# 07_-_CONNECTORS_2.net
KiCad netlist of a schematic drawn in Altium Designer
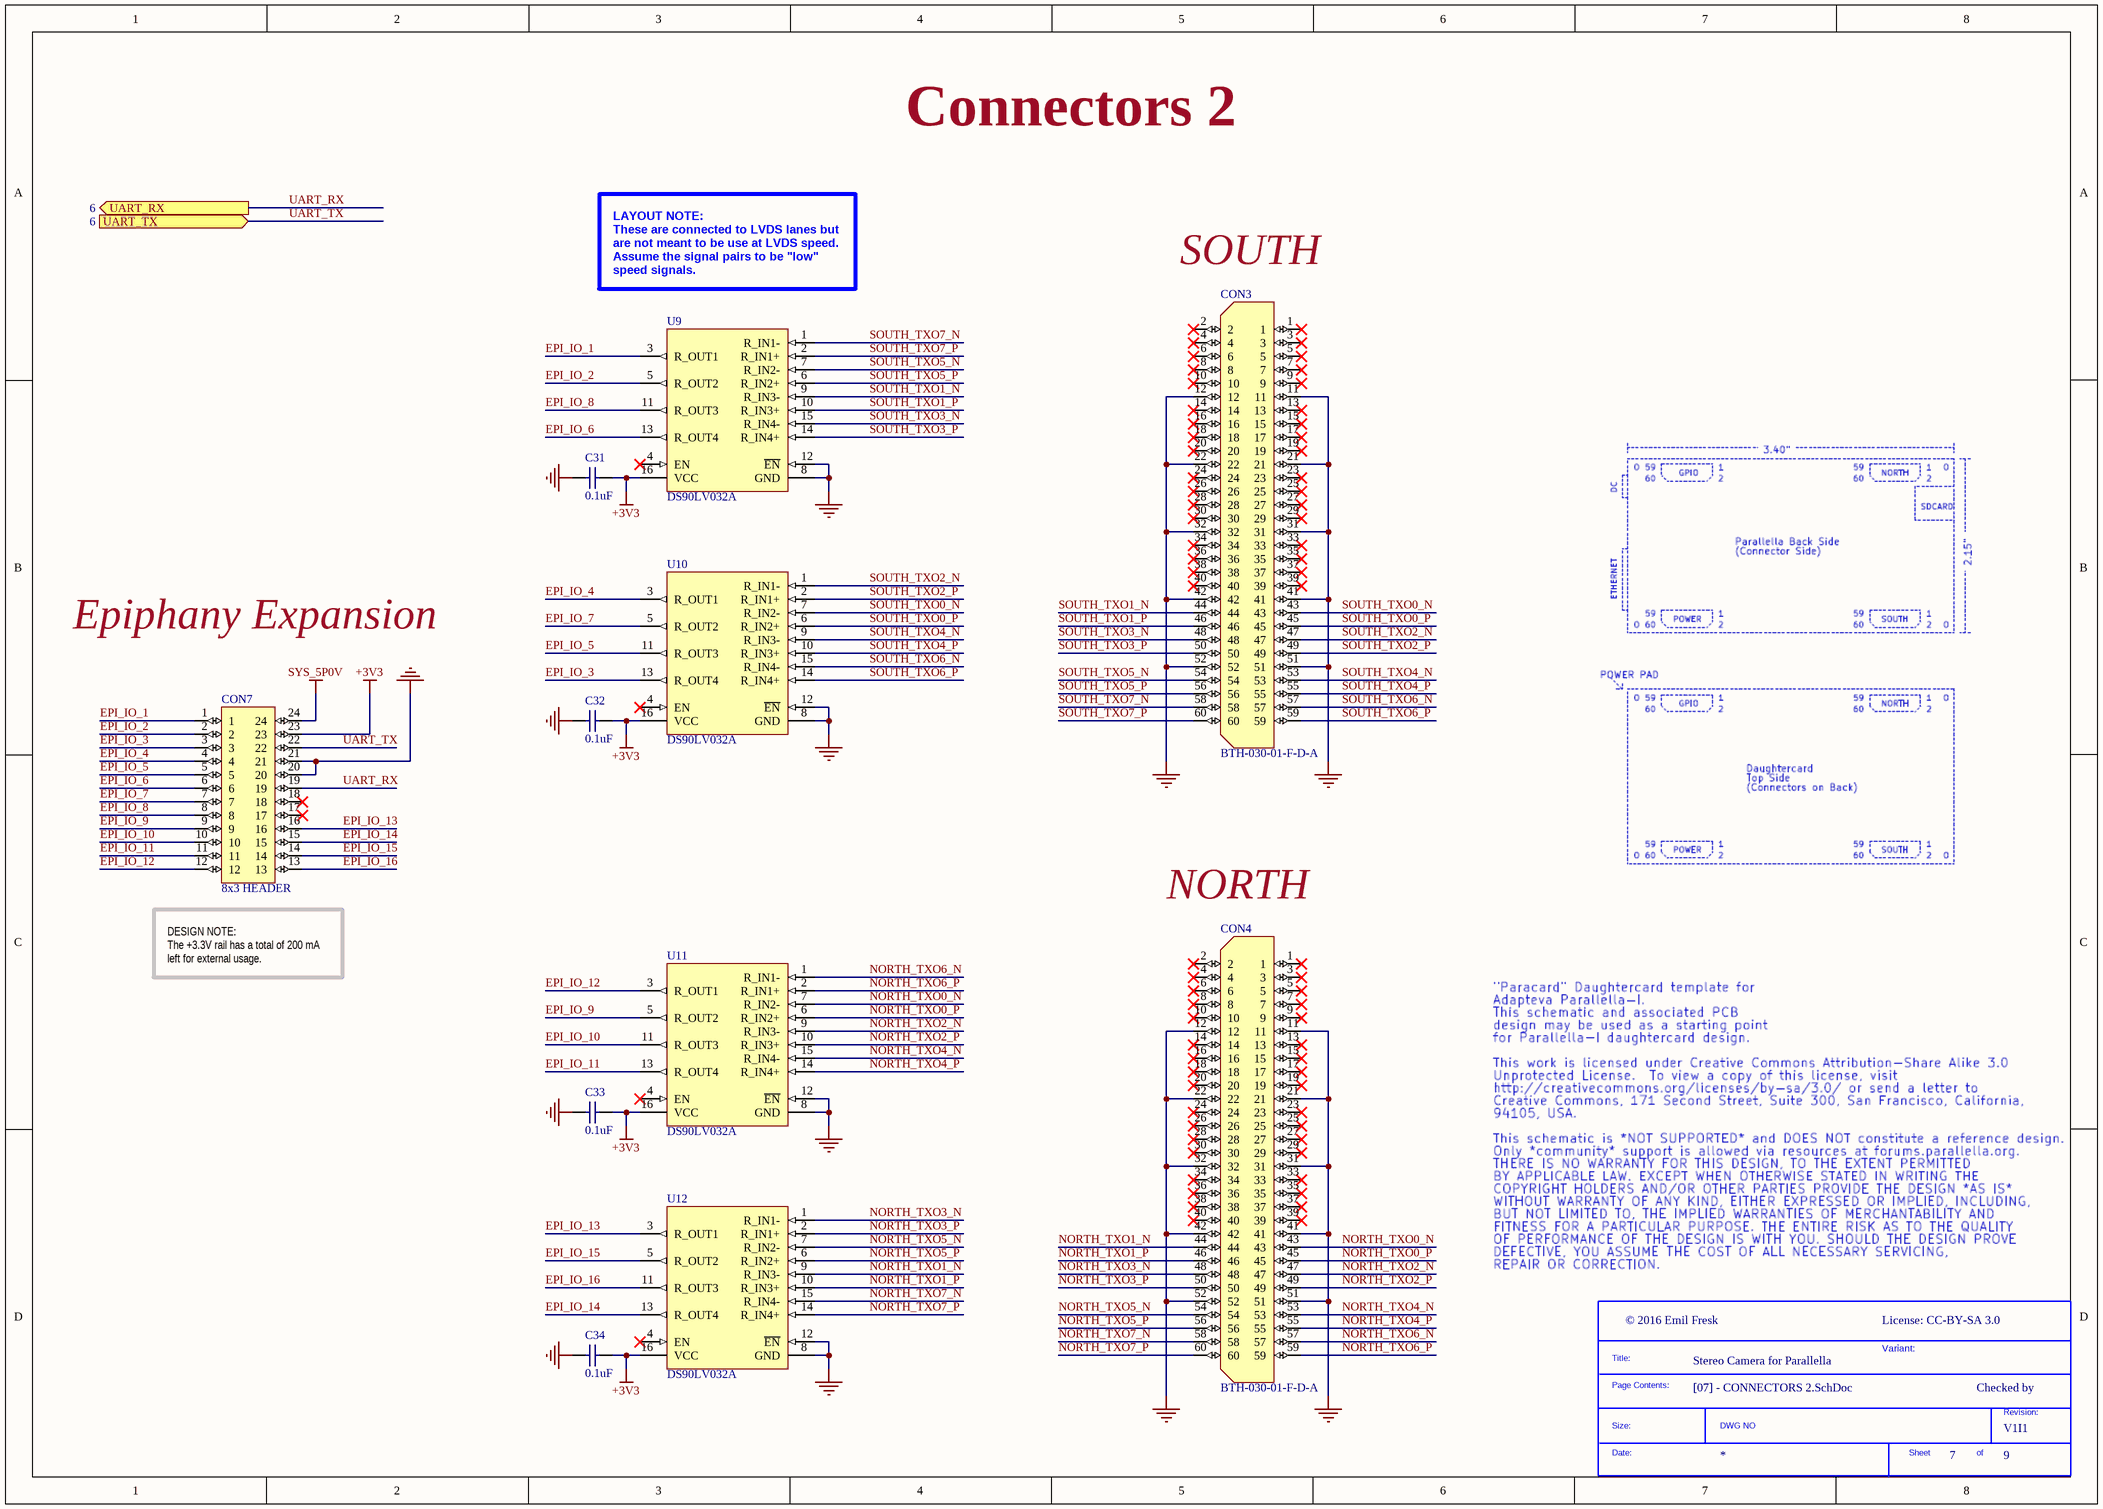
[diagram p0: [07] - CONNECTORS 2.SchDoc]

(export (version "E")
  (design (tool "Eeschema 10.0.6"))
  (components
    (comp (ref "C31")
      (value "0.1uF")
      (footprint "C0603L")
      (description "CAP CER 0.1UF 50V 10% X7R 0603")
      (fields
        (field (name "MANUFACTURER") "Murata Electronics North America")
        (field (name "MANUFACTURER PART NUMBER") "GRM188R71H104KA93J")
      )
      (libsource (lib "Capacitors") (part "GRM188R71H104KA93J"))
    )
    (comp (ref "C32")
      (value "0.1uF")
      (footprint "C0603L")
      (description "CAP CER 0.1UF 50V 10% X7R 0603")
      (fields
        (field (name "MANUFACTURER") "Murata Electronics North America")
        (field (name "MANUFACTURER PART NUMBER") "GRM188R71H104KA93J")
      )
      (libsource (lib "Capacitors") (part "GRM188R71H104KA93J"))
    )
    (comp (ref "C33")
      (value "0.1uF")
      (footprint "C0603L")
      (description "CAP CER 0.1UF 50V 10% X7R 0603")
      (fields
        (field (name "MANUFACTURER") "Murata Electronics North America")
        (field (name "MANUFACTURER PART NUMBER") "GRM188R71H104KA93J")
      )
      (libsource (lib "Capacitors") (part "GRM188R71H104KA93J"))
    )
    (comp (ref "C34")
      (value "0.1uF")
      (footprint "C0603L")
      (description "CAP CER 0.1UF 50V 10% X7R 0603")
      (fields
        (field (name "MANUFACTURER") "Murata Electronics North America")
        (field (name "MANUFACTURER PART NUMBER") "GRM188R71H104KA93J")
      )
      (libsource (lib "Capacitors") (part "GRM188R71H104KA93J"))
    )
    (comp (ref "CON3")
      (value "BTH-030-01-F-D-A")
      (footprint "BTH-030-01-X-D-A-K")
      (description "CONN RCPT 60POS 0.5MM SMD")
      (fields (field (name "MANUFACTURER") "Samtec Inc"))
      (libsource (lib "Connectors") (part "BTH-030-01-F-D-A"))
    )
    (comp (ref "CON4")
      (value "BTH-030-01-F-D-A")
      (footprint "BTH-030-01-X-D-A-K")
      (description "CONN RCPT 60POS 0.5MM SMD")
      (fields (field (name "MANUFACTURER") "Samtec Inc"))
      (libsource (lib "Connectors") (part "BTH-030-01-F-D-A"))
    )
    (comp (ref "CON7")
      (value "8x3 HEADER")
      (footprint "8x3HEADER_2.54mm")
      (libsource (lib "Connectors") (part "8x3 HEADER"))
    )
    (comp (ref "U9")
      (value "DS90LV032A")
      (footprint "TSSOP16N")
      (description "IC LINE RVR 3V QUAD DIFF 16TSSOP")
      (fields
        (field (name "MANUFACTURER") "Texas Instruments")
        (field (name "MANUFACTURER PART NUMBER") "DS90LV032ATMTCX/NOPB")
      )
      (libsource (lib "Level_Translators") (part "DS90LV032ATMTCX/NOPB"))
    )
    (comp (ref "U10")
      (value "DS90LV032A")
      (footprint "TSSOP16N")
      (description "IC LINE RVR 3V QUAD DIFF 16TSSOP")
      (fields
        (field (name "MANUFACTURER") "Texas Instruments")
        (field (name "MANUFACTURER PART NUMBER") "DS90LV032ATMTCX/NOPB")
      )
      (libsource (lib "Level_Translators") (part "DS90LV032ATMTCX/NOPB"))
    )
    (comp (ref "U11")
      (value "DS90LV032A")
      (footprint "TSSOP16N")
      (description "IC LINE RVR 3V QUAD DIFF 16TSSOP")
      (fields
        (field (name "MANUFACTURER") "Texas Instruments")
        (field (name "MANUFACTURER PART NUMBER") "DS90LV032ATMTCX/NOPB")
      )
      (libsource (lib "Level_Translators") (part "DS90LV032ATMTCX/NOPB"))
    )
    (comp (ref "U12")
      (value "DS90LV032A")
      (footprint "TSSOP16N")
      (description "IC LINE RVR 3V QUAD DIFF 16TSSOP")
      (fields
        (field (name "MANUFACTURER") "Texas Instruments")
        (field (name "MANUFACTURER PART NUMBER") "DS90LV032ATMTCX/NOPB")
      )
      (libsource (lib "Level_Translators") (part "DS90LV032ATMTCX/NOPB"))
    )
  )
  (nets
    (net (code "1") (name "+3V3") (class "Default")
      (node (ref "C31") (pin "2") (pinfunction "2_2") (pintype "passive"))
      (node (ref "C32") (pin "2") (pinfunction "2_2") (pintype "passive"))
      (node (ref "C33") (pin "2") (pinfunction "2_2") (pintype "passive"))
      (node (ref "C34") (pin "2") (pinfunction "2_2") (pintype "passive"))
      (node (ref "CON7") (pin "23") (pinfunction "23_23") (pintype "bidirectional"))
      (node (ref "U10") (pin "16") (pinfunction "VCC_16") (pintype "power_in"))
      (node (ref "U11") (pin "16") (pinfunction "VCC_16") (pintype "power_in"))
      (node (ref "U12") (pin "16") (pinfunction "VCC_16") (pintype "power_in"))
      (node (ref "U9") (pin "16") (pinfunction "VCC_16") (pintype "power_in"))
    )
    (net (code "2") (name "/EPI_IO_1") (class "Default")
      (node (ref "CON7") (pin "1") (pinfunction "1_1") (pintype "bidirectional"))
      (node (ref "U9") (pin "3") (pinfunction "R_OUT1_3") (pintype "output"))
    )
    (net (code "3") (name "/EPI_IO_2") (class "Default")
      (node (ref "CON7") (pin "2") (pinfunction "2_2") (pintype "bidirectional"))
      (node (ref "U9") (pin "5") (pinfunction "R_OUT2_5") (pintype "output"))
    )
    (net (code "4") (name "/EPI_IO_3") (class "Default")
      (node (ref "CON7") (pin "3") (pinfunction "3_3") (pintype "bidirectional"))
      (node (ref "U10") (pin "13") (pinfunction "R_OUT4_13") (pintype "output"))
    )
    (net (code "5") (name "/EPI_IO_4") (class "Default")
      (node (ref "CON7") (pin "4") (pinfunction "4_4") (pintype "bidirectional"))
      (node (ref "U10") (pin "3") (pinfunction "R_OUT1_3") (pintype "output"))
    )
    (net (code "6") (name "/EPI_IO_5") (class "Default")
      (node (ref "CON7") (pin "5") (pinfunction "5_5") (pintype "bidirectional"))
      (node (ref "U10") (pin "11") (pinfunction "R_OUT3_11") (pintype "output"))
    )
    (net (code "7") (name "/EPI_IO_6") (class "Default")
      (node (ref "CON7") (pin "6") (pinfunction "6_6") (pintype "bidirectional"))
      (node (ref "U9") (pin "13") (pinfunction "R_OUT4_13") (pintype "output"))
    )
    (net (code "8") (name "/EPI_IO_7") (class "Default")
      (node (ref "CON7") (pin "7") (pinfunction "7_7") (pintype "bidirectional"))
      (node (ref "U10") (pin "5") (pinfunction "R_OUT2_5") (pintype "output"))
    )
    (net (code "9") (name "/EPI_IO_8") (class "Default")
      (node (ref "CON7") (pin "8") (pinfunction "8_8") (pintype "bidirectional"))
      (node (ref "U9") (pin "11") (pinfunction "R_OUT3_11") (pintype "output"))
    )
    (net (code "10") (name "/EPI_IO_9") (class "Default")
      (node (ref "CON7") (pin "9") (pinfunction "9_9") (pintype "bidirectional"))
      (node (ref "U11") (pin "5") (pinfunction "R_OUT2_5") (pintype "output"))
    )
    (net (code "11") (name "/EPI_IO_10") (class "Default")
      (node (ref "CON7") (pin "10") (pinfunction "10_10") (pintype "bidirectional"))
      (node (ref "U11") (pin "11") (pinfunction "R_OUT3_11") (pintype "output"))
    )
    (net (code "12") (name "/EPI_IO_11") (class "Default")
      (node (ref "CON7") (pin "11") (pinfunction "11_11") (pintype "bidirectional"))
      (node (ref "U11") (pin "13") (pinfunction "R_OUT4_13") (pintype "output"))
    )
    (net (code "13") (name "/EPI_IO_12") (class "Default")
      (node (ref "CON7") (pin "12") (pinfunction "12_12") (pintype "bidirectional"))
      (node (ref "U11") (pin "3") (pinfunction "R_OUT1_3") (pintype "output"))
    )
    (net (code "14") (name "/EPI_IO_13") (class "Default")
      (node (ref "CON7") (pin "16") (pinfunction "16_16") (pintype "bidirectional"))
      (node (ref "U12") (pin "3") (pinfunction "R_OUT1_3") (pintype "output"))
    )
    (net (code "15") (name "/EPI_IO_14") (class "Default")
      (node (ref "CON7") (pin "15") (pinfunction "15_15") (pintype "bidirectional"))
      (node (ref "U12") (pin "13") (pinfunction "R_OUT4_13") (pintype "output"))
    )
    (net (code "16") (name "/EPI_IO_15") (class "Default")
      (node (ref "CON7") (pin "14") (pinfunction "14_14") (pintype "bidirectional"))
      (node (ref "U12") (pin "5") (pinfunction "R_OUT2_5") (pintype "output"))
    )
    (net (code "17") (name "/EPI_IO_16") (class "Default")
      (node (ref "CON7") (pin "13") (pinfunction "13_13") (pintype "bidirectional"))
      (node (ref "U12") (pin "11") (pinfunction "R_OUT3_11") (pintype "output"))
    )
    (net (code "18") (name "/NORTH_TXO0_N") (class "Default")
      (node (ref "CON4") (pin "43") (pinfunction "43_43") (pintype "bidirectional"))
      (node (ref "U11") (pin "7") (pinfunction "R_IN2-_7") (pintype "input"))
    )
    (net (code "19") (name "/NORTH_TXO0_P") (class "Default")
      (node (ref "CON4") (pin "45") (pinfunction "45_45") (pintype "bidirectional"))
      (node (ref "U11") (pin "6") (pinfunction "R_IN2+_6") (pintype "input"))
    )
    (net (code "20") (name "/NORTH_TXO1_N") (class "Default")
      (node (ref "CON4") (pin "44") (pinfunction "44_44") (pintype "bidirectional"))
      (node (ref "U12") (pin "9") (pinfunction "R_IN3-_9") (pintype "input"))
    )
    (net (code "21") (name "/NORTH_TXO1_P") (class "Default")
      (node (ref "CON4") (pin "46") (pinfunction "46_46") (pintype "bidirectional"))
      (node (ref "U12") (pin "10") (pinfunction "R_IN3+_10") (pintype "input"))
    )
    (net (code "22") (name "/NORTH_TXO2_N") (class "Default")
      (node (ref "CON4") (pin "47") (pinfunction "47_47") (pintype "bidirectional"))
      (node (ref "U11") (pin "9") (pinfunction "R_IN3-_9") (pintype "input"))
    )
    (net (code "23") (name "/NORTH_TXO2_P") (class "Default")
      (node (ref "CON4") (pin "49") (pinfunction "49_49") (pintype "bidirectional"))
      (node (ref "U11") (pin "10") (pinfunction "R_IN3+_10") (pintype "input"))
    )
    (net (code "24") (name "/NORTH_TXO3_N") (class "Default")
      (node (ref "CON4") (pin "48") (pinfunction "48_48") (pintype "bidirectional"))
      (node (ref "U12") (pin "1") (pinfunction "R_IN1-_1") (pintype "input"))
    )
    (net (code "25") (name "/NORTH_TXO3_P") (class "Default")
      (node (ref "CON4") (pin "50") (pinfunction "50_50") (pintype "bidirectional"))
      (node (ref "U12") (pin "2") (pinfunction "R_IN1+_2") (pintype "input"))
    )
    (net (code "26") (name "/NORTH_TXO4_N") (class "Default")
      (node (ref "CON4") (pin "53") (pinfunction "53_53") (pintype "bidirectional"))
      (node (ref "U11") (pin "15") (pinfunction "R_IN4-_15") (pintype "input"))
    )
    (net (code "27") (name "/NORTH_TXO4_P") (class "Default")
      (node (ref "CON4") (pin "55") (pinfunction "55_55") (pintype "bidirectional"))
      (node (ref "U11") (pin "14") (pinfunction "R_IN4+_14") (pintype "input"))
    )
    (net (code "28") (name "/NORTH_TXO5_N") (class "Default")
      (node (ref "CON4") (pin "54") (pinfunction "54_54") (pintype "bidirectional"))
      (node (ref "U12") (pin "7") (pinfunction "R_IN2-_7") (pintype "input"))
    )
    (net (code "29") (name "/NORTH_TXO5_P") (class "Default")
      (node (ref "CON4") (pin "56") (pinfunction "56_56") (pintype "bidirectional"))
      (node (ref "U12") (pin "6") (pinfunction "R_IN2+_6") (pintype "input"))
    )
    (net (code "30") (name "/NORTH_TXO6_N") (class "Default")
      (node (ref "CON4") (pin "57") (pinfunction "57_57") (pintype "bidirectional"))
      (node (ref "U11") (pin "1") (pinfunction "R_IN1-_1") (pintype "input"))
    )
    (net (code "31") (name "/NORTH_TXO6_P") (class "Default")
      (node (ref "CON4") (pin "59") (pinfunction "59_59") (pintype "bidirectional"))
      (node (ref "U11") (pin "2") (pinfunction "R_IN1+_2") (pintype "input"))
    )
    (net (code "32") (name "/NORTH_TXO7_N") (class "Default")
      (node (ref "CON4") (pin "58") (pinfunction "58_58") (pintype "bidirectional"))
      (node (ref "U12") (pin "15") (pinfunction "R_IN4-_15") (pintype "input"))
    )
    (net (code "33") (name "/NORTH_TXO7_P") (class "Default")
      (node (ref "CON4") (pin "60") (pinfunction "60_60") (pintype "bidirectional"))
      (node (ref "U12") (pin "14") (pinfunction "R_IN4+_14") (pintype "input"))
    )
    (net (code "34") (name "/SOUTH_TXO0_N") (class "Default")
      (node (ref "CON3") (pin "43") (pinfunction "43_43") (pintype "bidirectional"))
      (node (ref "U10") (pin "7") (pinfunction "R_IN2-_7") (pintype "input"))
    )
    (net (code "35") (name "/SOUTH_TXO0_P") (class "Default")
      (node (ref "CON3") (pin "45") (pinfunction "45_45") (pintype "bidirectional"))
      (node (ref "U10") (pin "6") (pinfunction "R_IN2+_6") (pintype "input"))
    )
    (net (code "36") (name "/SOUTH_TXO1_N") (class "Default")
      (node (ref "CON3") (pin "44") (pinfunction "44_44") (pintype "bidirectional"))
      (node (ref "U9") (pin "9") (pinfunction "R_IN3-_9") (pintype "input"))
    )
    (net (code "37") (name "/SOUTH_TXO1_P") (class "Default")
      (node (ref "CON3") (pin "46") (pinfunction "46_46") (pintype "bidirectional"))
      (node (ref "U9") (pin "10") (pinfunction "R_IN3+_10") (pintype "input"))
    )
    (net (code "38") (name "/SOUTH_TXO2_N") (class "Default")
      (node (ref "CON3") (pin "47") (pinfunction "47_47") (pintype "bidirectional"))
      (node (ref "U10") (pin "1") (pinfunction "R_IN1-_1") (pintype "input"))
    )
    (net (code "39") (name "/SOUTH_TXO2_P") (class "Default")
      (node (ref "CON3") (pin "49") (pinfunction "49_49") (pintype "bidirectional"))
      (node (ref "U10") (pin "2") (pinfunction "R_IN1+_2") (pintype "input"))
    )
    (net (code "40") (name "/SOUTH_TXO3_N") (class "Default")
      (node (ref "CON3") (pin "48") (pinfunction "48_48") (pintype "bidirectional"))
      (node (ref "U9") (pin "15") (pinfunction "R_IN4-_15") (pintype "input"))
    )
    (net (code "41") (name "/SOUTH_TXO3_P") (class "Default")
      (node (ref "CON3") (pin "50") (pinfunction "50_50") (pintype "bidirectional"))
      (node (ref "U9") (pin "14") (pinfunction "R_IN4+_14") (pintype "input"))
    )
    (net (code "42") (name "/SOUTH_TXO4_N") (class "Default")
      (node (ref "CON3") (pin "53") (pinfunction "53_53") (pintype "bidirectional"))
      (node (ref "U10") (pin "9") (pinfunction "R_IN3-_9") (pintype "input"))
    )
    (net (code "43") (name "/SOUTH_TXO4_P") (class "Default")
      (node (ref "CON3") (pin "55") (pinfunction "55_55") (pintype "bidirectional"))
      (node (ref "U10") (pin "10") (pinfunction "R_IN3+_10") (pintype "input"))
    )
    (net (code "44") (name "/SOUTH_TXO5_N") (class "Default")
      (node (ref "CON3") (pin "54") (pinfunction "54_54") (pintype "bidirectional"))
      (node (ref "U9") (pin "7") (pinfunction "R_IN2-_7") (pintype "input"))
    )
    (net (code "45") (name "/SOUTH_TXO5_P") (class "Default")
      (node (ref "CON3") (pin "56") (pinfunction "56_56") (pintype "bidirectional"))
      (node (ref "U9") (pin "6") (pinfunction "R_IN2+_6") (pintype "input"))
    )
    (net (code "46") (name "/SOUTH_TXO6_N") (class "Default")
      (node (ref "CON3") (pin "57") (pinfunction "57_57") (pintype "bidirectional"))
      (node (ref "U10") (pin "15") (pinfunction "R_IN4-_15") (pintype "input"))
    )
    (net (code "47") (name "/SOUTH_TXO6_P") (class "Default")
      (node (ref "CON3") (pin "59") (pinfunction "59_59") (pintype "bidirectional"))
      (node (ref "U10") (pin "14") (pinfunction "R_IN4+_14") (pintype "input"))
    )
    (net (code "48") (name "/SOUTH_TXO7_N") (class "Default")
      (node (ref "CON3") (pin "58") (pinfunction "58_58") (pintype "bidirectional"))
      (node (ref "U9") (pin "1") (pinfunction "R_IN1-_1") (pintype "input"))
    )
    (net (code "49") (name "/SOUTH_TXO7_P") (class "Default")
      (node (ref "CON3") (pin "60") (pinfunction "60_60") (pintype "bidirectional"))
      (node (ref "U9") (pin "2") (pinfunction "R_IN1+_2") (pintype "input"))
    )
    (net (code "50") (name "/UART_RX") (class "Default")
      (node (ref "CON7") (pin "19") (pinfunction "19_19") (pintype "bidirectional"))
    )
    (net (code "51") (name "/UART_TX") (class "Default")
      (node (ref "CON7") (pin "22") (pinfunction "22_22") (pintype "bidirectional"))
    )
    (net (code "52") (name "GND") (class "Default")
      (node (ref "C31") (pin "1") (pinfunction "1_1") (pintype "passive"))
      (node (ref "C32") (pin "1") (pinfunction "1_1") (pintype "passive"))
      (node (ref "C33") (pin "1") (pinfunction "1_1") (pintype "passive"))
      (node (ref "C34") (pin "1") (pinfunction "1_1") (pintype "passive"))
      (node (ref "CON3") (pin "11") (pinfunction "11_11") (pintype "bidirectional"))
      (node (ref "CON3") (pin "12") (pinfunction "12_12") (pintype "bidirectional"))
      (node (ref "CON3") (pin "21") (pinfunction "21_21") (pintype "bidirectional"))
      (node (ref "CON3") (pin "22") (pinfunction "22_22") (pintype "bidirectional"))
      (node (ref "CON3") (pin "31") (pinfunction "31_31") (pintype "bidirectional"))
      (node (ref "CON3") (pin "32") (pinfunction "32_32") (pintype "bidirectional"))
      (node (ref "CON3") (pin "41") (pinfunction "41_41") (pintype "bidirectional"))
      (node (ref "CON3") (pin "42") (pinfunction "42_42") (pintype "bidirectional"))
      (node (ref "CON3") (pin "51") (pinfunction "51_51") (pintype "bidirectional"))
      (node (ref "CON3") (pin "52") (pinfunction "52_52") (pintype "bidirectional"))
      (node (ref "CON4") (pin "11") (pinfunction "11_11") (pintype "bidirectional"))
      (node (ref "CON4") (pin "12") (pinfunction "12_12") (pintype "bidirectional"))
      (node (ref "CON4") (pin "21") (pinfunction "21_21") (pintype "bidirectional"))
      (node (ref "CON4") (pin "22") (pinfunction "22_22") (pintype "bidirectional"))
      (node (ref "CON4") (pin "31") (pinfunction "31_31") (pintype "bidirectional"))
      (node (ref "CON4") (pin "32") (pinfunction "32_32") (pintype "bidirectional"))
      (node (ref "CON4") (pin "41") (pinfunction "41_41") (pintype "bidirectional"))
      (node (ref "CON4") (pin "42") (pinfunction "42_42") (pintype "bidirectional"))
      (node (ref "CON4") (pin "51") (pinfunction "51_51") (pintype "bidirectional"))
      (node (ref "CON4") (pin "52") (pinfunction "52_52") (pintype "bidirectional"))
      (node (ref "CON7") (pin "20") (pinfunction "20_20") (pintype "bidirectional"))
      (node (ref "CON7") (pin "21") (pinfunction "21_21") (pintype "bidirectional"))
      (node (ref "U10") (pin "12") (pinfunction "~{EN}_12") (pintype "input"))
      (node (ref "U10") (pin "8") (pinfunction "GND_8") (pintype "power_in"))
      (node (ref "U11") (pin "12") (pinfunction "~{EN}_12") (pintype "input"))
      (node (ref "U11") (pin "8") (pinfunction "GND_8") (pintype "power_in"))
      (node (ref "U12") (pin "12") (pinfunction "~{EN}_12") (pintype "input"))
      (node (ref "U12") (pin "8") (pinfunction "GND_8") (pintype "power_in"))
      (node (ref "U9") (pin "12") (pinfunction "~{EN}_12") (pintype "input"))
      (node (ref "U9") (pin "8") (pinfunction "GND_8") (pintype "power_in"))
    )
    (net (code "53") (name "SYS_5P0V") (class "Default")
      (node (ref "CON7") (pin "24") (pinfunction "24_24") (pintype "bidirectional"))
    )
    (net (code "54") (name "unconnected-(CON3-Pad1)") (class "Default")
      (node (ref "CON3") (pin "1") (pinfunction "1_1") (pintype "bidirectional+no_connect"))
    )
    (net (code "55") (name "unconnected-(CON3-Pad2)") (class "Default")
      (node (ref "CON3") (pin "2") (pinfunction "2_2") (pintype "bidirectional+no_connect"))
    )
    (net (code "56") (name "unconnected-(CON3-Pad3)") (class "Default")
      (node (ref "CON3") (pin "3") (pinfunction "3_3") (pintype "bidirectional+no_connect"))
    )
    (net (code "57") (name "unconnected-(CON3-Pad4)") (class "Default")
      (node (ref "CON3") (pin "4") (pinfunction "4_4") (pintype "bidirectional+no_connect"))
    )
    (net (code "58") (name "unconnected-(CON3-Pad5)") (class "Default")
      (node (ref "CON3") (pin "5") (pinfunction "5_5") (pintype "bidirectional+no_connect"))
    )
    (net (code "59") (name "unconnected-(CON3-Pad6)") (class "Default")
      (node (ref "CON3") (pin "6") (pinfunction "6_6") (pintype "bidirectional+no_connect"))
    )
    (net (code "60") (name "unconnected-(CON3-Pad7)") (class "Default")
      (node (ref "CON3") (pin "7") (pinfunction "7_7") (pintype "bidirectional+no_connect"))
    )
    (net (code "61") (name "unconnected-(CON3-Pad8)") (class "Default")
      (node (ref "CON3") (pin "8") (pinfunction "8_8") (pintype "bidirectional+no_connect"))
    )
    (net (code "62") (name "unconnected-(CON3-Pad9)") (class "Default")
      (node (ref "CON3") (pin "9") (pinfunction "9_9") (pintype "bidirectional+no_connect"))
    )
    (net (code "63") (name "unconnected-(CON3-Pad10)") (class "Default")
      (node (ref "CON3") (pin "10") (pinfunction "10_10") (pintype "bidirectional+no_connect"))
    )
    (net (code "64") (name "unconnected-(CON3-Pad13)") (class "Default")
      (node (ref "CON3") (pin "13") (pinfunction "13_13") (pintype "bidirectional+no_connect"))
    )
    (net (code "65") (name "unconnected-(CON3-Pad14)") (class "Default")
      (node (ref "CON3") (pin "14") (pinfunction "14_14") (pintype "bidirectional+no_connect"))
    )
    (net (code "66") (name "unconnected-(CON3-Pad15)") (class "Default")
      (node (ref "CON3") (pin "15") (pinfunction "15_15") (pintype "bidirectional+no_connect"))
    )
    (net (code "67") (name "unconnected-(CON3-Pad16)") (class "Default")
      (node (ref "CON3") (pin "16") (pinfunction "16_16") (pintype "bidirectional+no_connect"))
    )
    (net (code "68") (name "unconnected-(CON3-Pad17)") (class "Default")
      (node (ref "CON3") (pin "17") (pinfunction "17_17") (pintype "bidirectional+no_connect"))
    )
    (net (code "69") (name "unconnected-(CON3-Pad18)") (class "Default")
      (node (ref "CON3") (pin "18") (pinfunction "18_18") (pintype "bidirectional+no_connect"))
    )
    (net (code "70") (name "unconnected-(CON3-Pad19)") (class "Default")
      (node (ref "CON3") (pin "19") (pinfunction "19_19") (pintype "bidirectional+no_connect"))
    )
    (net (code "71") (name "unconnected-(CON3-Pad20)") (class "Default")
      (node (ref "CON3") (pin "20") (pinfunction "20_20") (pintype "bidirectional+no_connect"))
    )
    (net (code "72") (name "unconnected-(CON3-Pad23)") (class "Default")
      (node (ref "CON3") (pin "23") (pinfunction "23_23") (pintype "bidirectional+no_connect"))
    )
    (net (code "73") (name "unconnected-(CON3-Pad24)") (class "Default")
      (node (ref "CON3") (pin "24") (pinfunction "24_24") (pintype "bidirectional+no_connect"))
    )
    (net (code "74") (name "unconnected-(CON3-Pad25)") (class "Default")
      (node (ref "CON3") (pin "25") (pinfunction "25_25") (pintype "bidirectional+no_connect"))
    )
    (net (code "75") (name "unconnected-(CON3-Pad26)") (class "Default")
      (node (ref "CON3") (pin "26") (pinfunction "26_26") (pintype "bidirectional+no_connect"))
    )
    (net (code "76") (name "unconnected-(CON3-Pad27)") (class "Default")
      (node (ref "CON3") (pin "27") (pinfunction "27_27") (pintype "bidirectional+no_connect"))
    )
    (net (code "77") (name "unconnected-(CON3-Pad28)") (class "Default")
      (node (ref "CON3") (pin "28") (pinfunction "28_28") (pintype "bidirectional+no_connect"))
    )
    (net (code "78") (name "unconnected-(CON3-Pad29)") (class "Default")
      (node (ref "CON3") (pin "29") (pinfunction "29_29") (pintype "bidirectional+no_connect"))
    )
    (net (code "79") (name "unconnected-(CON3-Pad30)") (class "Default")
      (node (ref "CON3") (pin "30") (pinfunction "30_30") (pintype "bidirectional+no_connect"))
    )
    (net (code "80") (name "unconnected-(CON3-Pad33)") (class "Default")
      (node (ref "CON3") (pin "33") (pinfunction "33_33") (pintype "bidirectional+no_connect"))
    )
    (net (code "81") (name "unconnected-(CON3-Pad34)") (class "Default")
      (node (ref "CON3") (pin "34") (pinfunction "34_34") (pintype "bidirectional+no_connect"))
    )
    (net (code "82") (name "unconnected-(CON3-Pad35)") (class "Default")
      (node (ref "CON3") (pin "35") (pinfunction "35_35") (pintype "bidirectional+no_connect"))
    )
    (net (code "83") (name "unconnected-(CON3-Pad36)") (class "Default")
      (node (ref "CON3") (pin "36") (pinfunction "36_36") (pintype "bidirectional+no_connect"))
    )
    (net (code "84") (name "unconnected-(CON3-Pad37)") (class "Default")
      (node (ref "CON3") (pin "37") (pinfunction "37_37") (pintype "bidirectional+no_connect"))
    )
    (net (code "85") (name "unconnected-(CON3-Pad38)") (class "Default")
      (node (ref "CON3") (pin "38") (pinfunction "38_38") (pintype "bidirectional+no_connect"))
    )
    (net (code "86") (name "unconnected-(CON3-Pad39)") (class "Default")
      (node (ref "CON3") (pin "39") (pinfunction "39_39") (pintype "bidirectional+no_connect"))
    )
    (net (code "87") (name "unconnected-(CON3-Pad40)") (class "Default")
      (node (ref "CON3") (pin "40") (pinfunction "40_40") (pintype "bidirectional+no_connect"))
    )
    (net (code "88") (name "unconnected-(CON4-Pad1)") (class "Default")
      (node (ref "CON4") (pin "1") (pinfunction "1_1") (pintype "bidirectional+no_connect"))
    )
    (net (code "89") (name "unconnected-(CON4-Pad2)") (class "Default")
      (node (ref "CON4") (pin "2") (pinfunction "2_2") (pintype "bidirectional+no_connect"))
    )
    (net (code "90") (name "unconnected-(CON4-Pad3)") (class "Default")
      (node (ref "CON4") (pin "3") (pinfunction "3_3") (pintype "bidirectional+no_connect"))
    )
    (net (code "91") (name "unconnected-(CON4-Pad4)") (class "Default")
      (node (ref "CON4") (pin "4") (pinfunction "4_4") (pintype "bidirectional+no_connect"))
    )
    (net (code "92") (name "unconnected-(CON4-Pad5)") (class "Default")
      (node (ref "CON4") (pin "5") (pinfunction "5_5") (pintype "bidirectional+no_connect"))
    )
    (net (code "93") (name "unconnected-(CON4-Pad6)") (class "Default")
      (node (ref "CON4") (pin "6") (pinfunction "6_6") (pintype "bidirectional+no_connect"))
    )
    (net (code "94") (name "unconnected-(CON4-Pad7)") (class "Default")
      (node (ref "CON4") (pin "7") (pinfunction "7_7") (pintype "bidirectional+no_connect"))
    )
    (net (code "95") (name "unconnected-(CON4-Pad8)") (class "Default")
      (node (ref "CON4") (pin "8") (pinfunction "8_8") (pintype "bidirectional+no_connect"))
    )
    (net (code "96") (name "unconnected-(CON4-Pad9)") (class "Default")
      (node (ref "CON4") (pin "9") (pinfunction "9_9") (pintype "bidirectional+no_connect"))
    )
    (net (code "97") (name "unconnected-(CON4-Pad10)") (class "Default")
      (node (ref "CON4") (pin "10") (pinfunction "10_10") (pintype "bidirectional+no_connect"))
    )
    (net (code "98") (name "unconnected-(CON4-Pad13)") (class "Default")
      (node (ref "CON4") (pin "13") (pinfunction "13_13") (pintype "bidirectional+no_connect"))
    )
    (net (code "99") (name "unconnected-(CON4-Pad14)") (class "Default")
      (node (ref "CON4") (pin "14") (pinfunction "14_14") (pintype "bidirectional+no_connect"))
    )
    (net (code "100") (name "unconnected-(CON4-Pad15)") (class "Default")
      (node (ref "CON4") (pin "15") (pinfunction "15_15") (pintype "bidirectional+no_connect"))
    )
    (net (code "101") (name "unconnected-(CON4-Pad16)") (class "Default")
      (node (ref "CON4") (pin "16") (pinfunction "16_16") (pintype "bidirectional+no_connect"))
    )
    (net (code "102") (name "unconnected-(CON4-Pad17)") (class "Default")
      (node (ref "CON4") (pin "17") (pinfunction "17_17") (pintype "bidirectional+no_connect"))
    )
    (net (code "103") (name "unconnected-(CON4-Pad18)") (class "Default")
      (node (ref "CON4") (pin "18") (pinfunction "18_18") (pintype "bidirectional+no_connect"))
    )
    (net (code "104") (name "unconnected-(CON4-Pad19)") (class "Default")
      (node (ref "CON4") (pin "19") (pinfunction "19_19") (pintype "bidirectional+no_connect"))
    )
    (net (code "105") (name "unconnected-(CON4-Pad20)") (class "Default")
      (node (ref "CON4") (pin "20") (pinfunction "20_20") (pintype "bidirectional+no_connect"))
    )
    (net (code "106") (name "unconnected-(CON4-Pad23)") (class "Default")
      (node (ref "CON4") (pin "23") (pinfunction "23_23") (pintype "bidirectional+no_connect"))
    )
    (net (code "107") (name "unconnected-(CON4-Pad24)") (class "Default")
      (node (ref "CON4") (pin "24") (pinfunction "24_24") (pintype "bidirectional+no_connect"))
    )
    (net (code "108") (name "unconnected-(CON4-Pad25)") (class "Default")
      (node (ref "CON4") (pin "25") (pinfunction "25_25") (pintype "bidirectional+no_connect"))
    )
    (net (code "109") (name "unconnected-(CON4-Pad26)") (class "Default")
      (node (ref "CON4") (pin "26") (pinfunction "26_26") (pintype "bidirectional+no_connect"))
    )
    (net (code "110") (name "unconnected-(CON4-Pad27)") (class "Default")
      (node (ref "CON4") (pin "27") (pinfunction "27_27") (pintype "bidirectional+no_connect"))
    )
    (net (code "111") (name "unconnected-(CON4-Pad28)") (class "Default")
      (node (ref "CON4") (pin "28") (pinfunction "28_28") (pintype "bidirectional+no_connect"))
    )
    (net (code "112") (name "unconnected-(CON4-Pad29)") (class "Default")
      (node (ref "CON4") (pin "29") (pinfunction "29_29") (pintype "bidirectional+no_connect"))
    )
    (net (code "113") (name "unconnected-(CON4-Pad30)") (class "Default")
      (node (ref "CON4") (pin "30") (pinfunction "30_30") (pintype "bidirectional+no_connect"))
    )
    (net (code "114") (name "unconnected-(CON4-Pad33)") (class "Default")
      (node (ref "CON4") (pin "33") (pinfunction "33_33") (pintype "bidirectional+no_connect"))
    )
    (net (code "115") (name "unconnected-(CON4-Pad34)") (class "Default")
      (node (ref "CON4") (pin "34") (pinfunction "34_34") (pintype "bidirectional+no_connect"))
    )
    (net (code "116") (name "unconnected-(CON4-Pad35)") (class "Default")
      (node (ref "CON4") (pin "35") (pinfunction "35_35") (pintype "bidirectional+no_connect"))
    )
    (net (code "117") (name "unconnected-(CON4-Pad36)") (class "Default")
      (node (ref "CON4") (pin "36") (pinfunction "36_36") (pintype "bidirectional+no_connect"))
    )
    (net (code "118") (name "unconnected-(CON4-Pad37)") (class "Default")
      (node (ref "CON4") (pin "37") (pinfunction "37_37") (pintype "bidirectional+no_connect"))
    )
    (net (code "119") (name "unconnected-(CON4-Pad38)") (class "Default")
      (node (ref "CON4") (pin "38") (pinfunction "38_38") (pintype "bidirectional+no_connect"))
    )
    (net (code "120") (name "unconnected-(CON4-Pad39)") (class "Default")
      (node (ref "CON4") (pin "39") (pinfunction "39_39") (pintype "bidirectional+no_connect"))
    )
    (net (code "121") (name "unconnected-(CON4-Pad40)") (class "Default")
      (node (ref "CON4") (pin "40") (pinfunction "40_40") (pintype "bidirectional+no_connect"))
    )
    (net (code "122") (name "unconnected-(CON7-Pad17)") (class "Default")
      (node (ref "CON7") (pin "17") (pinfunction "17_17") (pintype "bidirectional+no_connect"))
    )
    (net (code "123") (name "unconnected-(CON7-Pad18)") (class "Default")
      (node (ref "CON7") (pin "18") (pinfunction "18_18") (pintype "bidirectional+no_connect"))
    )
    (net (code "124") (name "unconnected-(U9-EN-Pad4)") (class "Default")
      (node (ref "U9") (pin "4") (pinfunction "EN_4") (pintype "input+no_connect"))
    )
    (net (code "125") (name "unconnected-(U10-EN-Pad4)") (class "Default")
      (node (ref "U10") (pin "4") (pinfunction "EN_4") (pintype "input+no_connect"))
    )
    (net (code "126") (name "unconnected-(U11-EN-Pad4)") (class "Default")
      (node (ref "U11") (pin "4") (pinfunction "EN_4") (pintype "input+no_connect"))
    )
    (net (code "127") (name "unconnected-(U12-EN-Pad4)") (class "Default")
      (node (ref "U12") (pin "4") (pinfunction "EN_4") (pintype "input+no_connect"))
    )
  )
)
